# 3_ports.net
KiCad netlist of a schematic drawn in Altium Designer
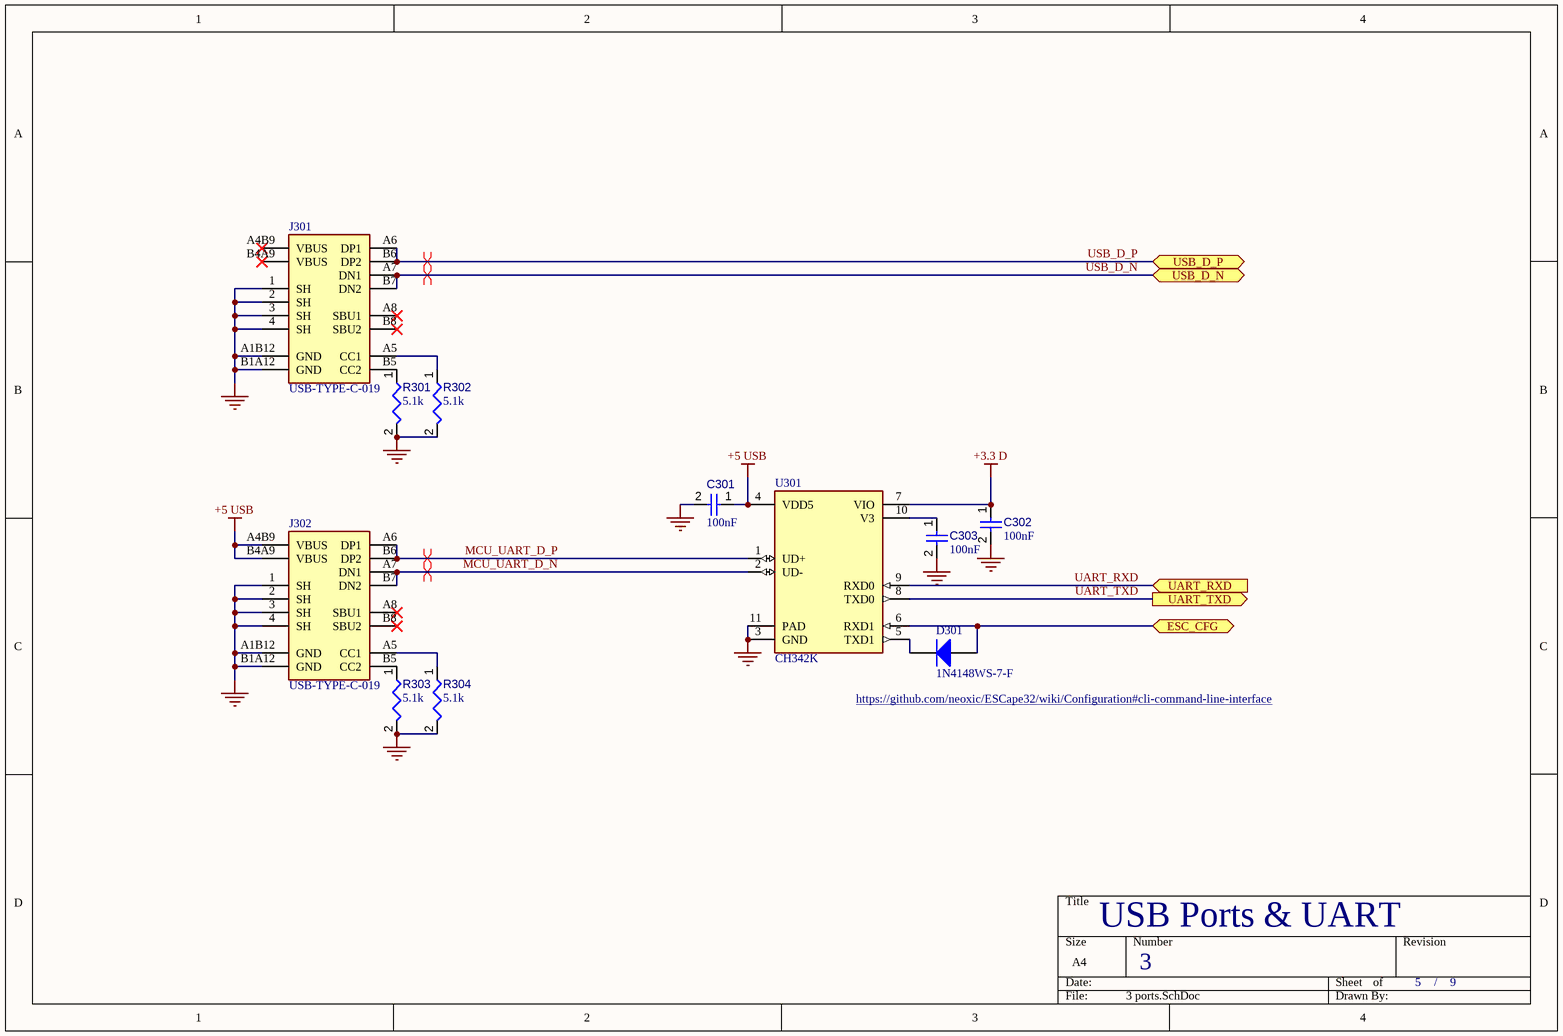
[diagram p0: 3 ports.SchDoc]

(export (version "E")
  (design (tool "Eeschema 10.0.6"))
  (components
    (comp (ref "C301")
      (value "100nF")
      (footprint "CAPC0402(1005)60_L")
      (description "Chip Capacitor, 100nF +/-20%, 25V, 0402, Thickness 0.6 mm")
      (fields (field (name "TOLERANCE") "10%") (field (name "Comment") "Capacitor 100nF +/-20% 25V 0402"))
      (libsource (lib "UBC Uncrewed Aircraft Systems") (part "CAP-NP-2"))
    )
    (comp (ref "C302")
      (value "100nF")
      (footprint "CAPC0402(1005)60_L")
      (description "Chip Capacitor, 100nF +/-20%, 25V, 0402, Thickness 0.6 mm")
      (fields (field (name "TOLERANCE") "10%") (field (name "Comment") "Capacitor 100nF +/-20% 25V 0402"))
      (libsource (lib "UBC Uncrewed Aircraft Systems") (part "CAP-NP-2"))
    )
    (comp (ref "C303")
      (value "100nF")
      (footprint "CAPC0402(1005)60_L")
      (description "Chip Capacitor, 100nF +/-20%, 25V, 0402, Thickness 0.6 mm")
      (fields (field (name "TOLERANCE") "10%") (field (name "Comment") "Capacitor 100nF +/-20% 25V 0402"))
      (libsource (lib "UBC Uncrewed Aircraft Systems") (part "CAP-NP-2"))
    )
    (comp (ref "D301")
      (value "1N4148WS-7-F")
      (footprint "DIOD-SOD323-2-A_V")
      (description "Fast Switching Diode, 75 V, 0.3 A, -65 to 150 degC, 2-Pin SOD323, RoHS, Tape and Reel")
      (libsource (lib "Altium Content Vault") (part "D-AK-2"))
    )
    (comp (ref "J301")
      (value "USB-TYPE-C-019")
      (footprint "USB-TYPE-C-12+4P")
      (fields (field (name "MANUFACTURER") "DEALON(德艺隆)"))
      (libsource (lib "JLCPCB Library") (part "USB-TYPE-C-019"))
    )
    (comp (ref "J302")
      (value "USB-TYPE-C-019")
      (footprint "USB-TYPE-C-12+4P")
      (fields (field (name "MANUFACTURER") "DEALON(德艺隆)"))
      (libsource (lib "JLCPCB Library") (part "USB-TYPE-C-019"))
    )
    (comp (ref "R301")
      (value "5.1k")
      (footprint "RESC0402(1005)_L")
      (description "Chip Resistor, 5.1 kOhms, +/-1 %, 63 mW, -55 to 155 degC, 0402")
      (fields (field (name "POWER") "63mW") (field (name "TOLERANCE") "1%"))
      (libsource (lib "UBC Uncrewed Aircraft Systems") (part "RES-2"))
    )
    (comp (ref "R302")
      (value "5.1k")
      (footprint "RESC0402(1005)_L")
      (description "Chip Resistor, 5.1 kOhms, +/-1 %, 63 mW, -55 to 155 degC, 0402")
      (fields (field (name "POWER") "63mW") (field (name "TOLERANCE") "1%"))
      (libsource (lib "UBC Uncrewed Aircraft Systems") (part "RES-2"))
    )
    (comp (ref "R303")
      (value "5.1k")
      (footprint "RESC0402(1005)_L")
      (description "Chip Resistor, 5.1 kOhms, +/-1 %, 63 mW, -55 to 155 degC, 0402")
      (fields (field (name "POWER") "63mW") (field (name "TOLERANCE") "1%"))
      (libsource (lib "UBC Uncrewed Aircraft Systems") (part "RES-2"))
    )
    (comp (ref "R304")
      (value "5.1k")
      (footprint "RESC0402(1005)_L")
      (description "Chip Resistor, 5.1 kOhms, +/-1 %, 63 mW, -55 to 155 degC, 0402")
      (fields (field (name "POWER") "63mW") (field (name "TOLERANCE") "1%"))
      (libsource (lib "UBC Uncrewed Aircraft Systems") (part "RES-2"))
    )
    (comp (ref "U301")
      (value "CH342K")
      (footprint "SSOP-10_L5.0-W3.9-P1.00-LS6.0-BL-EP")
      (description "ESSOP-10-150mil USB Converters ROHS")
      (libsource (lib "JLCPCB Library") (part "CH342K"))
    )
  )
  (nets
    (net (code "1") (name "+3.3 D") (class "Default")
      (node (ref "C302") (pin "1") (pinfunction "1_1") (pintype "passive"))
      (node (ref "U301") (pin "7") (pinfunction "VIO_7") (pintype "power_in"))
    )
    (net (code "2") (name "+5 USB") (class "Default")
      (node (ref "C301") (pin "1") (pinfunction "1_1") (pintype "passive"))
      (node (ref "J302") (pin "A4B9") (pinfunction "VBUS_A4B9") (pintype "power_in"))
      (node (ref "J302") (pin "B4A9") (pinfunction "VBUS_B4A9") (pintype "power_in"))
      (node (ref "U301") (pin "4") (pinfunction "VDD5_4") (pintype "power_in"))
    )
    (net (code "3") (name "/ESC_CFG") (class "Default")
      (node (ref "D301") (pin "1") (pinfunction "A_1") (pintype "passive"))
      (node (ref "U301") (pin "6") (pinfunction "RXD1_6") (pintype "input"))
    )
    (net (code "4") (name "/MCU_UART_D_N") (class "Default")
      (node (ref "J302") (pin "A7") (pinfunction "DN1_A7") (pintype "passive"))
      (node (ref "J302") (pin "B7") (pinfunction "DN2_B7") (pintype "passive"))
      (node (ref "U301") (pin "2") (pinfunction "UD-_2") (pintype "bidirectional"))
    )
    (net (code "5") (name "/MCU_UART_D_P") (class "Default")
      (node (ref "J302") (pin "A6") (pinfunction "DP1_A6") (pintype "passive"))
      (node (ref "J302") (pin "B6") (pinfunction "DP2_B6") (pintype "passive"))
      (node (ref "U301") (pin "1") (pinfunction "UD+_1") (pintype "bidirectional"))
    )
    (net (code "6") (name "/UART_RXD") (class "Default")
      (node (ref "U301") (pin "9") (pinfunction "RXD0_9") (pintype "input"))
    )
    (net (code "7") (name "/UART_TXD") (class "Default")
      (node (ref "U301") (pin "8") (pinfunction "TXD0_8") (pintype "output"))
    )
    (net (code "8") (name "/USB_D_N") (class "Default")
      (node (ref "J301") (pin "A7") (pinfunction "DN1_A7") (pintype "passive"))
      (node (ref "J301") (pin "B7") (pinfunction "DN2_B7") (pintype "passive"))
    )
    (net (code "9") (name "/USB_D_P") (class "Default")
      (node (ref "J301") (pin "A6") (pinfunction "DP1_A6") (pintype "passive"))
      (node (ref "J301") (pin "B6") (pinfunction "DP2_B6") (pintype "passive"))
    )
    (net (code "10") (name "GND") (class "Default")
      (node (ref "C301") (pin "2") (pinfunction "2_2") (pintype "passive"))
      (node (ref "C302") (pin "2") (pinfunction "2_2") (pintype "passive"))
      (node (ref "C303") (pin "2") (pinfunction "2_2") (pintype "passive"))
      (node (ref "J301") (pin "1") (pinfunction "SH_1") (pintype "passive"))
      (node (ref "J301") (pin "2") (pinfunction "SH_2") (pintype "passive"))
      (node (ref "J301") (pin "3") (pinfunction "SH_3") (pintype "passive"))
      (node (ref "J301") (pin "4") (pinfunction "SH_4") (pintype "passive"))
      (node (ref "J301") (pin "A1B12") (pinfunction "GND_A1B12") (pintype "power_in"))
      (node (ref "J301") (pin "B1A12") (pinfunction "GND_B1A12") (pintype "power_in"))
      (node (ref "J302") (pin "1") (pinfunction "SH_1") (pintype "passive"))
      (node (ref "J302") (pin "2") (pinfunction "SH_2") (pintype "passive"))
      (node (ref "J302") (pin "3") (pinfunction "SH_3") (pintype "passive"))
      (node (ref "J302") (pin "4") (pinfunction "SH_4") (pintype "passive"))
      (node (ref "J302") (pin "A1B12") (pinfunction "GND_A1B12") (pintype "power_in"))
      (node (ref "J302") (pin "B1A12") (pinfunction "GND_B1A12") (pintype "power_in"))
      (node (ref "R301") (pin "2") (pinfunction "2_2") (pintype "passive"))
      (node (ref "R302") (pin "2") (pinfunction "2_2") (pintype "passive"))
      (node (ref "R303") (pin "2") (pinfunction "2_2") (pintype "passive"))
      (node (ref "R304") (pin "2") (pinfunction "2_2") (pintype "passive"))
      (node (ref "U301") (pin "11") (pinfunction "PAD_11") (pintype "power_in"))
      (node (ref "U301") (pin "3") (pinfunction "GND_3") (pintype "power_in"))
    )
    (net (code "11") (name "Net-(D301-K)") (class "Default")
      (node (ref "D301") (pin "2") (pinfunction "K_2") (pintype "passive"))
      (node (ref "U301") (pin "5") (pinfunction "TXD1_5") (pintype "output"))
    )
    (net (code "12") (name "Net-(J301-CC1)") (class "Default")
      (node (ref "J301") (pin "A5") (pinfunction "CC1_A5") (pintype "passive"))
      (node (ref "R302") (pin "1") (pinfunction "1_1") (pintype "passive"))
    )
    (net (code "13") (name "Net-(J301-CC2)") (class "Default")
      (node (ref "J301") (pin "B5") (pinfunction "CC2_B5") (pintype "passive"))
      (node (ref "R301") (pin "1") (pinfunction "1_1") (pintype "passive"))
    )
    (net (code "14") (name "Net-(J302-CC1)") (class "Default")
      (node (ref "J302") (pin "A5") (pinfunction "CC1_A5") (pintype "passive"))
      (node (ref "R304") (pin "1") (pinfunction "1_1") (pintype "passive"))
    )
    (net (code "15") (name "Net-(J302-CC2)") (class "Default")
      (node (ref "J302") (pin "B5") (pinfunction "CC2_B5") (pintype "passive"))
      (node (ref "R303") (pin "1") (pinfunction "1_1") (pintype "passive"))
    )
    (net (code "16") (name "Net-(U301-V3)") (class "Default")
      (node (ref "C303") (pin "1") (pinfunction "1_1") (pintype "passive"))
      (node (ref "U301") (pin "10") (pinfunction "V3_10") (pintype "power_in"))
    )
    (net (code "17") (name "unconnected-(J301-SBU1-PadA8)") (class "Default")
      (node (ref "J301") (pin "A8") (pinfunction "SBU1_A8") (pintype "passive+no_connect"))
    )
    (net (code "18") (name "unconnected-(J301-SBU2-PadB8)") (class "Default")
      (node (ref "J301") (pin "B8") (pinfunction "SBU2_B8") (pintype "passive+no_connect"))
    )
    (net (code "19") (name "unconnected-(J301-VBUS-PadA4B9)") (class "Default")
      (node (ref "J301") (pin "A4B9") (pinfunction "VBUS_A4B9") (pintype "power_in+no_connect"))
    )
    (net (code "20") (name "unconnected-(J301-VBUS-PadB4A9)") (class "Default")
      (node (ref "J301") (pin "B4A9") (pinfunction "VBUS_B4A9") (pintype "power_in+no_connect"))
    )
    (net (code "21") (name "unconnected-(J302-SBU1-PadA8)") (class "Default")
      (node (ref "J302") (pin "A8") (pinfunction "SBU1_A8") (pintype "passive+no_connect"))
    )
    (net (code "22") (name "unconnected-(J302-SBU2-PadB8)") (class "Default")
      (node (ref "J302") (pin "B8") (pinfunction "SBU2_B8") (pintype "passive+no_connect"))
    )
  )
)
